# AA8513.net
KiCad netlist of a schematic drawn in Altium Designer
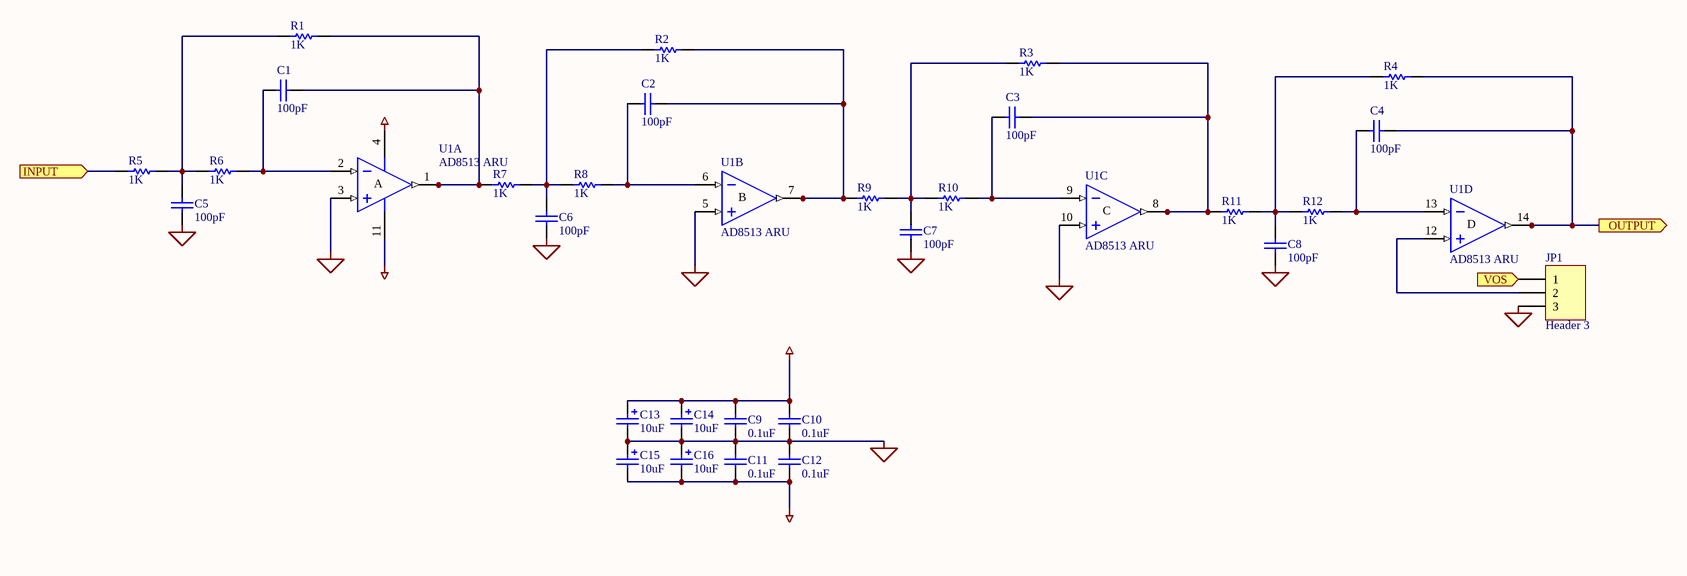
[diagram p0: AA8513.SCHDOC]

(export (version "E")
  (design (tool "Eeschema 10.0.6"))
  (components
    (comp (ref "C1")
      (value "Cap")
      (footprint "CC3216-1206")
      (description "Capacitor")
      (fields
        (field (name "MANUFACTURER") "Generic Components")
        (field (name "ALTIUM_VALUE") "100pF")
        (field (name "PUBLISHER") "Altium Limited")
      )
      (libsource (lib "Miscellaneous Devices") (part "Cap"))
    )
    (comp (ref "C2")
      (value "Cap")
      (footprint "CC3216-1206")
      (description "Capacitor")
      (fields
        (field (name "MANUFACTURER") "Generic Components")
        (field (name "ALTIUM_VALUE") "100pF")
        (field (name "PUBLISHER") "Altium Limited")
      )
      (libsource (lib "Miscellaneous Devices") (part "Cap"))
    )
    (comp (ref "C3")
      (value "Cap")
      (footprint "CC3216-1206")
      (description "Capacitor")
      (fields
        (field (name "MANUFACTURER") "Generic Components")
        (field (name "ALTIUM_VALUE") "100pF")
        (field (name "PUBLISHER") "Altium Limited")
      )
      (libsource (lib "Miscellaneous Devices") (part "Cap"))
    )
    (comp (ref "C4")
      (value "Cap")
      (footprint "CC3216-1206")
      (description "Capacitor")
      (fields
        (field (name "MANUFACTURER") "Generic Components")
        (field (name "ALTIUM_VALUE") "100pF")
        (field (name "PUBLISHER") "Altium Limited")
      )
      (libsource (lib "Miscellaneous Devices") (part "Cap"))
    )
    (comp (ref "C5")
      (value "Cap")
      (footprint "CC3216-1206")
      (description "Capacitor")
      (fields
        (field (name "MANUFACTURER") "Generic Components")
        (field (name "ALTIUM_VALUE") "100pF")
        (field (name "PUBLISHER") "Altium Limited")
      )
      (libsource (lib "Miscellaneous Devices") (part "Cap"))
    )
    (comp (ref "C6")
      (value "Cap")
      (footprint "CC3216-1206")
      (description "Capacitor")
      (fields
        (field (name "MANUFACTURER") "Generic Components")
        (field (name "ALTIUM_VALUE") "100pF")
        (field (name "PUBLISHER") "Altium Limited")
      )
      (libsource (lib "Miscellaneous Devices") (part "Cap"))
    )
    (comp (ref "C7")
      (value "Cap")
      (footprint "CC3216-1206")
      (description "Capacitor")
      (fields
        (field (name "MANUFACTURER") "Generic Components")
        (field (name "ALTIUM_VALUE") "100pF")
        (field (name "PUBLISHER") "Altium Limited")
      )
      (libsource (lib "Miscellaneous Devices") (part "Cap"))
    )
    (comp (ref "C8")
      (value "Cap")
      (footprint "CC3216-1206")
      (description "Capacitor")
      (fields
        (field (name "MANUFACTURER") "Generic Components")
        (field (name "ALTIUM_VALUE") "100pF")
        (field (name "PUBLISHER") "Altium Limited")
      )
      (libsource (lib "Miscellaneous Devices") (part "Cap"))
    )
    (comp (ref "C9")
      (value "Cap")
      (footprint "CC1608-0603")
      (description "Capacitor")
      (fields
        (field (name "MANUFACTURER") "Generic Components")
        (field (name "ALTIUM_VALUE") "0.1uF")
        (field (name "PUBLISHER") "Altium Limited")
      )
      (libsource (lib "Miscellaneous Devices") (part "Cap"))
    )
    (comp (ref "C10")
      (value "Cap")
      (footprint "CC1608-0603")
      (description "Capacitor")
      (fields
        (field (name "MANUFACTURER") "Generic Components")
        (field (name "ALTIUM_VALUE") "0.1uF")
        (field (name "PUBLISHER") "Altium Limited")
      )
      (libsource (lib "Miscellaneous Devices") (part "Cap"))
    )
    (comp (ref "C11")
      (value "Cap")
      (footprint "CC1608-0603")
      (description "Capacitor")
      (fields
        (field (name "MANUFACTURER") "Generic Components")
        (field (name "ALTIUM_VALUE") "0.1uF")
        (field (name "PUBLISHER") "Altium Limited")
      )
      (libsource (lib "Miscellaneous Devices") (part "Cap"))
    )
    (comp (ref "C12")
      (value "Cap")
      (footprint "CC1608-0603")
      (description "Capacitor")
      (fields
        (field (name "MANUFACTURER") "Generic Components")
        (field (name "ALTIUM_VALUE") "0.1uF")
        (field (name "PUBLISHER") "Altium Limited")
      )
      (libsource (lib "Miscellaneous Devices") (part "Cap"))
    )
    (comp (ref "C13")
      (value "Cap Pol1")
      (footprint "TC7360-2924")
      (description "Polarized Capacitor (Radial)")
      (fields
        (field (name "MANUFACTURER") "Generic Components")
        (field (name "ALTIUM_VALUE") "10uF")
        (field (name "PUBLISHER") "Altium Limited")
      )
      (libsource (lib "Miscellaneous Devices") (part "Cap Pol1"))
    )
    (comp (ref "C14")
      (value "Cap Pol1")
      (footprint "TC7360-2924")
      (description "Polarized Capacitor (Radial)")
      (fields
        (field (name "MANUFACTURER") "Generic Components")
        (field (name "ALTIUM_VALUE") "10uF")
        (field (name "PUBLISHER") "Altium Limited")
      )
      (libsource (lib "Miscellaneous Devices") (part "Cap Pol1"))
    )
    (comp (ref "C15")
      (value "Cap Pol1")
      (footprint "TC7360-2924")
      (description "Polarized Capacitor (Radial)")
      (fields
        (field (name "MANUFACTURER") "Generic Components")
        (field (name "ALTIUM_VALUE") "10uF")
        (field (name "PUBLISHER") "Altium Limited")
      )
      (libsource (lib "Miscellaneous Devices") (part "Cap Pol1"))
    )
    (comp (ref "C16")
      (value "Cap Pol1")
      (footprint "TC7360-2924")
      (description "Polarized Capacitor (Radial)")
      (fields
        (field (name "MANUFACTURER") "Generic Components")
        (field (name "ALTIUM_VALUE") "10uF")
        (field (name "PUBLISHER") "Altium Limited")
      )
      (libsource (lib "Miscellaneous Devices") (part "Cap Pol1"))
    )
    (comp (ref "JP1")
      (value "Header 3")
      (footprint "HDR1X3")
      (description "Header, 3-Pin")
      (fields (field (name "MANUFACTURER") "Generic Components") (field (name "PUBLISHER") "Altium Limited"))
      (libsource (lib "Miscellaneous Connectors") (part "Header 3"))
    )
    (comp (ref "R1")
      (value "Res1")
      (footprint "CC2012-0805")
      (description "Resistor")
      (fields
        (field (name "MANUFACTURER") "Generic Components")
        (field (name "ALTIUM_VALUE") "1K")
        (field (name "PUBLISHER") "Altium Limited")
      )
      (libsource (lib "Miscellaneous Devices") (part "Res1"))
    )
    (comp (ref "R2")
      (value "Res1")
      (footprint "CC2012-0805")
      (description "Resistor")
      (fields
        (field (name "MANUFACTURER") "Generic Components")
        (field (name "ALTIUM_VALUE") "1K")
        (field (name "PUBLISHER") "Altium Limited")
      )
      (libsource (lib "Miscellaneous Devices") (part "Res1"))
    )
    (comp (ref "R3")
      (value "Res1")
      (footprint "CC2012-0805")
      (description "Resistor")
      (fields
        (field (name "MANUFACTURER") "Generic Components")
        (field (name "ALTIUM_VALUE") "1K")
        (field (name "PUBLISHER") "Altium Limited")
      )
      (libsource (lib "Miscellaneous Devices") (part "Res1"))
    )
    (comp (ref "R4")
      (value "Res1")
      (footprint "CC2012-0805")
      (description "Resistor")
      (fields
        (field (name "MANUFACTURER") "Generic Components")
        (field (name "ALTIUM_VALUE") "1K")
        (field (name "PUBLISHER") "Altium Limited")
      )
      (libsource (lib "Miscellaneous Devices") (part "Res1"))
    )
    (comp (ref "R5")
      (value "Res1")
      (footprint "CC2012-0805")
      (description "Resistor")
      (fields
        (field (name "MANUFACTURER") "Generic Components")
        (field (name "ALTIUM_VALUE") "1K")
        (field (name "PUBLISHER") "Altium Limited")
      )
      (libsource (lib "Miscellaneous Devices") (part "Res1"))
    )
    (comp (ref "R6")
      (value "Res1")
      (footprint "CC2012-0805")
      (description "Resistor")
      (fields
        (field (name "MANUFACTURER") "Generic Components")
        (field (name "ALTIUM_VALUE") "1K")
        (field (name "PUBLISHER") "Altium Limited")
      )
      (libsource (lib "Miscellaneous Devices") (part "Res1"))
    )
    (comp (ref "R7")
      (value "Res1")
      (footprint "CC2012-0805")
      (description "Resistor")
      (fields
        (field (name "MANUFACTURER") "Generic Components")
        (field (name "ALTIUM_VALUE") "1K")
        (field (name "PUBLISHER") "Altium Limited")
      )
      (libsource (lib "Miscellaneous Devices") (part "Res1"))
    )
    (comp (ref "R8")
      (value "Res1")
      (footprint "CC2012-0805")
      (description "Resistor")
      (fields
        (field (name "MANUFACTURER") "Generic Components")
        (field (name "ALTIUM_VALUE") "1K")
        (field (name "PUBLISHER") "Altium Limited")
      )
      (libsource (lib "Miscellaneous Devices") (part "Res1"))
    )
    (comp (ref "R9")
      (value "Res1")
      (footprint "CC2012-0805")
      (description "Resistor")
      (fields
        (field (name "MANUFACTURER") "Generic Components")
        (field (name "ALTIUM_VALUE") "1K")
        (field (name "PUBLISHER") "Altium Limited")
      )
      (libsource (lib "Miscellaneous Devices") (part "Res1"))
    )
    (comp (ref "R10")
      (value "Res1")
      (footprint "CC2012-0805")
      (description "Resistor")
      (fields
        (field (name "MANUFACTURER") "Generic Components")
        (field (name "ALTIUM_VALUE") "1K")
        (field (name "PUBLISHER") "Altium Limited")
      )
      (libsource (lib "Miscellaneous Devices") (part "Res1"))
    )
    (comp (ref "R11")
      (value "Res1")
      (footprint "CC2012-0805")
      (description "Resistor")
      (fields
        (field (name "MANUFACTURER") "Generic Components")
        (field (name "ALTIUM_VALUE") "1K")
        (field (name "PUBLISHER") "Altium Limited")
      )
      (libsource (lib "Miscellaneous Devices") (part "Res1"))
    )
    (comp (ref "R12")
      (value "Res1")
      (footprint "CC2012-0805")
      (description "Resistor")
      (fields
        (field (name "MANUFACTURER") "Generic Components")
        (field (name "ALTIUM_VALUE") "1K")
        (field (name "PUBLISHER") "Altium Limited")
      )
      (libsource (lib "Miscellaneous Devices") (part "Res1"))
    )
    (comp (ref "U1")
      (value "AD8513 ARU")
      (footprint "TSSO5X6-G14/X.3")
      (description "low-noise JFET quad OA")
      (libsource (lib "My devices") (part "AD8513ARU"))
    )
  )
  (nets
    (net (code "1") (name "/INPUT") (class "Default")
      (node (ref "R5") (pin "1") (pinfunction "1_1") (pintype "passive"))
    )
    (net (code "2") (name "/OUTPUT") (class "Default")
      (node (ref "C4") (pin "1") (pinfunction "1_1") (pintype "passive"))
      (node (ref "R4") (pin "1") (pinfunction "1_1") (pintype "passive"))
      (node (ref "U1") (pin "14") (pinfunction "OUTD_14") (pintype "output"))
    )
    (net (code "3") (name "/VOS") (class "Default")
      (node (ref "JP1") (pin "1") (pinfunction "1_1") (pintype "passive"))
    )
    (net (code "4") (name "AVDD") (class "Default")
      (node (ref "C10") (pin "2") (pinfunction "2_2") (pintype "passive"))
      (node (ref "C13") (pin "1") (pinfunction "1_1") (pintype "passive"))
      (node (ref "C14") (pin "1") (pinfunction "1_1") (pintype "passive"))
      (node (ref "C9") (pin "2") (pinfunction "2_2") (pintype "passive"))
      (node (ref "U1") (pin "4") (pinfunction "V+_4") (pintype "power_in"))
    )
    (net (code "5") (name "AVSS") (class "Default")
      (node (ref "C11") (pin "1") (pinfunction "1_1") (pintype "passive"))
      (node (ref "C12") (pin "1") (pinfunction "1_1") (pintype "passive"))
      (node (ref "C15") (pin "2") (pinfunction "2_2") (pintype "passive"))
      (node (ref "C16") (pin "2") (pinfunction "2_2") (pintype "passive"))
      (node (ref "U1") (pin "11") (pinfunction "V-_11") (pintype "power_in"))
    )
    (net (code "6") (name "GND") (class "Default")
      (node (ref "C10") (pin "1") (pinfunction "1_1") (pintype "passive"))
      (node (ref "C11") (pin "2") (pinfunction "2_2") (pintype "passive"))
      (node (ref "C12") (pin "2") (pinfunction "2_2") (pintype "passive"))
      (node (ref "C13") (pin "2") (pinfunction "2_2") (pintype "passive"))
      (node (ref "C14") (pin "2") (pinfunction "2_2") (pintype "passive"))
      (node (ref "C15") (pin "1") (pinfunction "1_1") (pintype "passive"))
      (node (ref "C16") (pin "1") (pinfunction "1_1") (pintype "passive"))
      (node (ref "C5") (pin "1") (pinfunction "1_1") (pintype "passive"))
      (node (ref "C6") (pin "1") (pinfunction "1_1") (pintype "passive"))
      (node (ref "C7") (pin "1") (pinfunction "1_1") (pintype "passive"))
      (node (ref "C8") (pin "1") (pinfunction "1_1") (pintype "passive"))
      (node (ref "C9") (pin "1") (pinfunction "1_1") (pintype "passive"))
      (node (ref "JP1") (pin "3") (pinfunction "3_3") (pintype "passive"))
      (node (ref "U1") (pin "10") (pinfunction "IN+C_10") (pintype "input"))
      (node (ref "U1") (pin "3") (pinfunction "IN+A_3") (pintype "input"))
      (node (ref "U1") (pin "5") (pinfunction "IN+B_5") (pintype "input"))
    )
    (net (code "7") (name "Net-(C5-Pad2)") (class "Default")
      (node (ref "C5") (pin "2") (pinfunction "2_2") (pintype "passive"))
      (node (ref "R1") (pin "2") (pinfunction "2_2") (pintype "passive"))
      (node (ref "R5") (pin "2") (pinfunction "2_2") (pintype "passive"))
      (node (ref "R6") (pin "1") (pinfunction "1_1") (pintype "passive"))
    )
    (net (code "8") (name "Net-(C6-Pad2)") (class "Default")
      (node (ref "C6") (pin "2") (pinfunction "2_2") (pintype "passive"))
      (node (ref "R2") (pin "2") (pinfunction "2_2") (pintype "passive"))
      (node (ref "R7") (pin "2") (pinfunction "2_2") (pintype "passive"))
      (node (ref "R8") (pin "1") (pinfunction "1_1") (pintype "passive"))
    )
    (net (code "9") (name "Net-(C7-Pad2)") (class "Default")
      (node (ref "C7") (pin "2") (pinfunction "2_2") (pintype "passive"))
      (node (ref "R10") (pin "1") (pinfunction "1_1") (pintype "passive"))
      (node (ref "R3") (pin "2") (pinfunction "2_2") (pintype "passive"))
      (node (ref "R9") (pin "2") (pinfunction "2_2") (pintype "passive"))
    )
    (net (code "10") (name "Net-(C8-Pad2)") (class "Default")
      (node (ref "C8") (pin "2") (pinfunction "2_2") (pintype "passive"))
      (node (ref "R11") (pin "2") (pinfunction "2_2") (pintype "passive"))
      (node (ref "R12") (pin "1") (pinfunction "1_1") (pintype "passive"))
      (node (ref "R4") (pin "2") (pinfunction "2_2") (pintype "passive"))
    )
    (net (code "11") (name "Net-(U1A-IN-A)") (class "Default")
      (node (ref "C1") (pin "2") (pinfunction "2_2") (pintype "passive"))
      (node (ref "R6") (pin "2") (pinfunction "2_2") (pintype "passive"))
      (node (ref "U1") (pin "2") (pinfunction "IN-A_2") (pintype "input"))
    )
    (net (code "12") (name "Net-(U1A-OUTA)") (class "Default")
      (node (ref "C1") (pin "1") (pinfunction "1_1") (pintype "passive"))
      (node (ref "R1") (pin "1") (pinfunction "1_1") (pintype "passive"))
      (node (ref "R7") (pin "1") (pinfunction "1_1") (pintype "passive"))
      (node (ref "U1") (pin "1") (pinfunction "OUTA_1") (pintype "output"))
    )
    (net (code "13") (name "Net-(U1B-IN-B)") (class "Default")
      (node (ref "C2") (pin "2") (pinfunction "2_2") (pintype "passive"))
      (node (ref "R8") (pin "2") (pinfunction "2_2") (pintype "passive"))
      (node (ref "U1") (pin "6") (pinfunction "IN-B_6") (pintype "input"))
    )
    (net (code "14") (name "Net-(U1B-OUTB)") (class "Default")
      (node (ref "C2") (pin "1") (pinfunction "1_1") (pintype "passive"))
      (node (ref "R2") (pin "1") (pinfunction "1_1") (pintype "passive"))
      (node (ref "R9") (pin "1") (pinfunction "1_1") (pintype "passive"))
      (node (ref "U1") (pin "7") (pinfunction "OUTB_7") (pintype "output"))
    )
    (net (code "15") (name "Net-(U1C-IN-C)") (class "Default")
      (node (ref "C3") (pin "2") (pinfunction "2_2") (pintype "passive"))
      (node (ref "R10") (pin "2") (pinfunction "2_2") (pintype "passive"))
      (node (ref "U1") (pin "9") (pinfunction "IN-C_9") (pintype "input"))
    )
    (net (code "16") (name "Net-(U1C-OUTC)") (class "Default")
      (node (ref "C3") (pin "1") (pinfunction "1_1") (pintype "passive"))
      (node (ref "R11") (pin "1") (pinfunction "1_1") (pintype "passive"))
      (node (ref "R3") (pin "1") (pinfunction "1_1") (pintype "passive"))
      (node (ref "U1") (pin "8") (pinfunction "OUTC_8") (pintype "output"))
    )
    (net (code "17") (name "Net-(U1D-IN+D)") (class "Default")
      (node (ref "JP1") (pin "2") (pinfunction "2_2") (pintype "passive"))
      (node (ref "U1") (pin "12") (pinfunction "IN+D_12") (pintype "input"))
    )
    (net (code "18") (name "Net-(U1D-IN-D)") (class "Default")
      (node (ref "C4") (pin "2") (pinfunction "2_2") (pintype "passive"))
      (node (ref "R12") (pin "2") (pinfunction "2_2") (pintype "passive"))
      (node (ref "U1") (pin "13") (pinfunction "IN-D_13") (pintype "input"))
    )
  )
)
